# e202var-receiver-v1.net
KiCad netlist of a schematic drawn in EAGLE
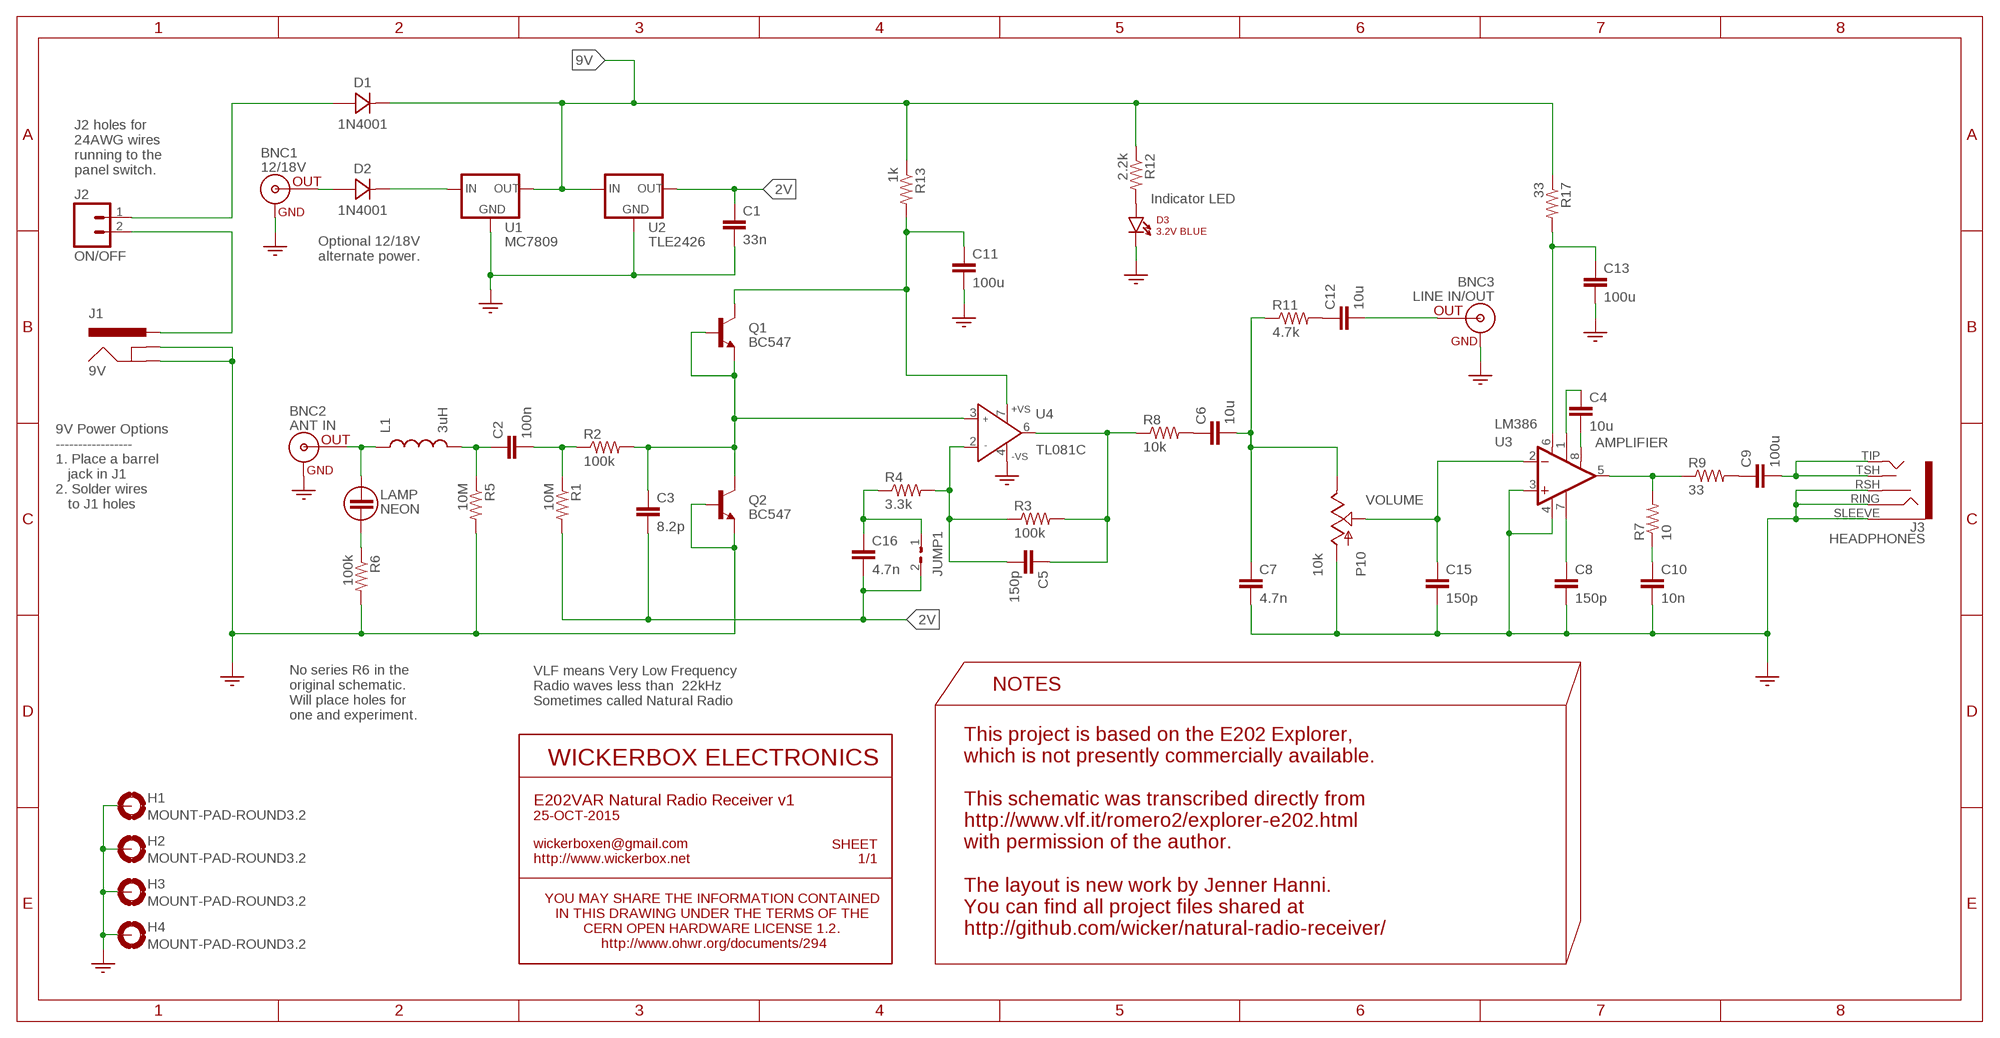
[diagram p0: schematic, sheet 1]

(export (version "E")
  (design (tool "Eeschema 10.0.6"))
  (components
    (comp (ref "BNC1")
      (value "12/18V")
      (footprint "eagle-import:BNC-MOLEX-SD-73100")
      (libsource (lib "eagle-import") (part "BNC-MOLEX-SD-73100"))
    )
    (comp (ref "BNC2")
      (value "ANT IN")
      (footprint "eagle-import:BNC-MOLEX-SD-73100")
      (libsource (lib "eagle-import") (part "BNC-MOLEX-SD-73100"))
    )
    (comp (ref "BNC3")
      (value "LINE IN/OUT")
      (footprint "eagle-import:BNC-MOLEX-SD-73100")
      (libsource (lib "eagle-import") (part "BNC-MOLEX-SD-73100"))
    )
    (comp (ref "C1")
      (value "33n")
      (footprint "eagle-import:CAP-RADIAL-5MM-NONPOL")
      (libsource (lib "eagle-import") (part "CAPACITOR5MM"))
    )
    (comp (ref "C2")
      (value "100n")
      (footprint "eagle-import:CAP-RADIAL-5MM-NONPOL")
      (libsource (lib "eagle-import") (part "CAPACITOR5MM"))
    )
    (comp (ref "C3")
      (value "8.2p")
      (footprint "eagle-import:CAP-RADIAL-5MM-NONPOL")
      (libsource (lib "eagle-import") (part "CAPACITOR5MM"))
    )
    (comp (ref "C4")
      (value "10u")
      (footprint "eagle-import:CAP-RADIAL-2.5MM-NONPOL")
      (libsource (lib "eagle-import") (part "CAPACITOR2.5MM"))
    )
    (comp (ref "C5")
      (value "150p")
      (footprint "eagle-import:CAP-RADIAL-2.5MM-NONPOL")
      (libsource (lib "eagle-import") (part "CAPACITOR2.5MM"))
    )
    (comp (ref "C6")
      (value "10u")
      (footprint "eagle-import:CAP-RADIAL-2.5MM-NONPOL")
      (libsource (lib "eagle-import") (part "CAPACITOR2.5MM"))
    )
    (comp (ref "C7")
      (value "4.7n")
      (footprint "eagle-import:CAP-RADIAL-5MM-NONPOL")
      (libsource (lib "eagle-import") (part "CAPACITOR5MM"))
    )
    (comp (ref "C8")
      (value "150p")
      (footprint "eagle-import:CAP-RADIAL-2.5MM-NONPOL")
      (libsource (lib "eagle-import") (part "CAPACITOR2.5MM"))
    )
    (comp (ref "C9")
      (value "100u")
      (footprint "eagle-import:CAP-RADIAL-5MM-NONPOL")
      (libsource (lib "eagle-import") (part "CAPACITOR5MM"))
    )
    (comp (ref "C10")
      (value "10n")
      (footprint "eagle-import:CAP-RADIAL-2.5MM-NONPOL")
      (libsource (lib "eagle-import") (part "CAPACITOR2.5MM"))
    )
    (comp (ref "C11")
      (value "100u")
      (footprint "eagle-import:CAP-RADIAL-5MM-NONPOL")
      (libsource (lib "eagle-import") (part "CAPACITOR5MM"))
    )
    (comp (ref "C12")
      (value "10u")
      (footprint "eagle-import:CAP-RADIAL-2.5MM-NONPOL")
      (libsource (lib "eagle-import") (part "CAPACITOR2.5MM"))
    )
    (comp (ref "C13")
      (value "100u")
      (footprint "eagle-import:CAP-RADIAL-5MM-NONPOL")
      (libsource (lib "eagle-import") (part "CAPACITOR5MM"))
    )
    (comp (ref "C15")
      (value "150p")
      (footprint "eagle-import:CAP-RADIAL-2.5MM-NONPOL")
      (libsource (lib "eagle-import") (part "CAPACITOR2.5MM"))
    )
    (comp (ref "C16")
      (value "4.7n")
      (footprint "eagle-import:CAP-RADIAL-5MM-NONPOL")
      (libsource (lib "eagle-import") (part "CAPACITOR5MM"))
    )
    (comp (ref "D1")
      (value "1N4001")
      (footprint "eagle-import:DIODE-DO41")
      (libsource (lib "eagle-import") (part "DIODE"))
    )
    (comp (ref "D2")
      (value "1N4001")
      (footprint "eagle-import:DIODE-DO41")
      (libsource (lib "eagle-import") (part "DIODE"))
    )
    (comp (ref "D3")
      (value "3.2V BLUE")
      (footprint "eagle-import:LED-2PIN-0.1IN")
      (libsource (lib "eagle-import") (part "LED"))
    )
    (comp (ref "H1")
      (value "MOUNT-PAD-ROUND3.2")
      (footprint "eagle-import:3,2-PAD")
      (libsource (lib "eagle-import") (part "MOUNT-PAD-ROUND3.2"))
    )
    (comp (ref "H2")
      (value "MOUNT-PAD-ROUND3.2")
      (footprint "eagle-import:3,2-PAD")
      (libsource (lib "eagle-import") (part "MOUNT-PAD-ROUND3.2"))
    )
    (comp (ref "H3")
      (value "MOUNT-PAD-ROUND3.2")
      (footprint "eagle-import:3,2-PAD")
      (libsource (lib "eagle-import") (part "MOUNT-PAD-ROUND3.2"))
    )
    (comp (ref "H4")
      (value "MOUNT-PAD-ROUND3.2")
      (footprint "eagle-import:3,2-PAD")
      (libsource (lib "eagle-import") (part "MOUNT-PAD-ROUND3.2"))
    )
    (comp (ref "J1")
      (value "9V")
      (footprint "eagle-import:JACK-POWER")
      (libsource (lib "eagle-import") (part "JACK-POWER-BARREL"))
    )
    (comp (ref "J2")
      (value "ON/OFF")
      (footprint "eagle-import:CONN-2PIN-0.1IN")
      (libsource (lib "eagle-import") (part "CONN-2PIN"))
    )
    (comp (ref "J3")
      (value "HEADPHONES")
      (footprint "eagle-import:JACK-AUDIO-5PIN")
      (libsource (lib "eagle-import") (part "JACK-AUDIO"))
    )
    (comp (ref "JUMP1")
      (value "HPF")
      (footprint "eagle-import:CONN-2PIN-0.1IN")
      (libsource (lib "eagle-import") (part "JUMPER-SHUNT"))
    )
    (comp (ref "L1")
      (value "3uH")
      (footprint "eagle-import:RES-CF14-TH")
      (libsource (lib "eagle-import") (part "INDUCTOR"))
    )
    (comp (ref "LAMP")
      (value "NEON")
      (footprint "eagle-import:LAMP-2PIN-0.1IN")
      (libsource (lib "eagle-import") (part "LAMP-NEON"))
    )
    (comp (ref "P10")
      (value "10k")
      (footprint "eagle-import:POT-3PIN-LINEAR")
      (libsource (lib "eagle-import") (part "POT-P160KN-0QC15B10K"))
    )
    (comp (ref "Q1")
      (value "BC547")
      (footprint "eagle-import:TO-92-AMMO")
      (libsource (lib "eagle-import") (part "BJT-NPN"))
    )
    (comp (ref "Q2")
      (value "BC547")
      (footprint "eagle-import:TO-92-AMMO")
      (libsource (lib "eagle-import") (part "BJT-NPN"))
    )
    (comp (ref "R1")
      (value "10M")
      (footprint "eagle-import:RES-CF14-TH")
      (libsource (lib "eagle-import") (part "RESISTOR"))
    )
    (comp (ref "R2")
      (value "100k")
      (footprint "eagle-import:RES-CF14-TH")
      (libsource (lib "eagle-import") (part "RESISTOR"))
    )
    (comp (ref "R3")
      (value "100k")
      (footprint "eagle-import:RES-CF14-TH")
      (libsource (lib "eagle-import") (part "RESISTOR"))
    )
    (comp (ref "R4")
      (value "3.3k")
      (footprint "eagle-import:RES-CF14-TH")
      (libsource (lib "eagle-import") (part "RESISTOR"))
    )
    (comp (ref "R5")
      (value "10M")
      (footprint "eagle-import:RES-CF14-TH")
      (libsource (lib "eagle-import") (part "RESISTOR"))
    )
    (comp (ref "R6")
      (value "100k")
      (footprint "eagle-import:RES-CF14-TH")
      (libsource (lib "eagle-import") (part "RESISTOR"))
    )
    (comp (ref "R7")
      (value "10")
      (footprint "eagle-import:RES-CF14-TH")
      (libsource (lib "eagle-import") (part "RESISTOR"))
    )
    (comp (ref "R8")
      (value "10k")
      (footprint "eagle-import:RES-CF14-TH")
      (libsource (lib "eagle-import") (part "RESISTOR"))
    )
    (comp (ref "R9")
      (value "33")
      (footprint "eagle-import:RES-CF14-TH")
      (libsource (lib "eagle-import") (part "RESISTOR"))
    )
    (comp (ref "R11")
      (value "4.7k")
      (footprint "eagle-import:RES-CF14-TH")
      (libsource (lib "eagle-import") (part "RESISTOR"))
    )
    (comp (ref "R12")
      (value "2.2k")
      (footprint "eagle-import:RES-CF14-TH")
      (libsource (lib "eagle-import") (part "RESISTOR"))
    )
    (comp (ref "R13")
      (value "1k")
      (footprint "eagle-import:RES-CF14-TH")
      (libsource (lib "eagle-import") (part "RESISTOR"))
    )
    (comp (ref "R17")
      (value "33")
      (footprint "eagle-import:RES-CF14-TH")
      (libsource (lib "eagle-import") (part "RESISTOR"))
    )
    (comp (ref "U1")
      (value "MC7809")
      (footprint "eagle-import:TO-220")
      (libsource (lib "eagle-import") (part "VOLTREG-MC7809"))
    )
    (comp (ref "U2")
      (value "TLE2426")
      (footprint "eagle-import:DIP-08")
      (libsource (lib "eagle-import") (part "VOLTREG-TLE2426"))
    )
    (comp (ref "U3")
      (value "LM386")
      (footprint "eagle-import:DIP-08")
      (libsource (lib "eagle-import") (part "AMP-AUDIO-LM386"))
    )
    (comp (ref "U4")
      (value "TL081C")
      (footprint "eagle-import:DIP-08")
      (libsource (lib "eagle-import") (part "AMP-JFET-TL081CP"))
    )
  )
  (nets
    (net (code "1") (name "2V") (class "Default")
      (node (ref "C1") (pin "1") (pinfunction "1_1") (pintype "passive"))
      (node (ref "C16") (pin "2") (pinfunction "2_2") (pintype "passive"))
      (node (ref "C3") (pin "2") (pinfunction "2_2") (pintype "passive"))
      (node (ref "JUMP1") (pin "2") (pinfunction "2_2") (pintype "passive"))
      (node (ref "R1") (pin "P$2") (pinfunction "2_P$2") (pintype "passive"))
      (node (ref "U2") (pin "1") (pinfunction "OUT_1") (pintype "output"))
    )
    (net (code "2") (name "9V") (class "Default")
      (node (ref "D1") (pin "C") (pinfunction "CATHODE_C") (pintype "passive"))
      (node (ref "R12") (pin "P$1") (pinfunction "1_P$1") (pintype "passive"))
      (node (ref "R13") (pin "P$1") (pinfunction "1_P$1") (pintype "passive"))
      (node (ref "R17") (pin "P$1") (pinfunction "1_P$1") (pintype "passive"))
      (node (ref "U1") (pin "OUT") (pinfunction "OUT_OUT") (pintype "output"))
      (node (ref "U2") (pin "3") (pinfunction "IN_3") (pintype "input"))
    )
    (net (code "3") (name "GND") (class "Default")
      (node (ref "BNC1") (pin "GND") (pinfunction "GND_GND") (pintype "bidirectional"))
      (node (ref "BNC1") (pin "GND1") (pinfunction "GND_GND1") (pintype "bidirectional"))
      (node (ref "BNC2") (pin "GND") (pinfunction "GND_GND") (pintype "bidirectional"))
      (node (ref "BNC2") (pin "GND1") (pinfunction "GND_GND1") (pintype "bidirectional"))
      (node (ref "BNC3") (pin "GND") (pinfunction "GND_GND") (pintype "bidirectional"))
      (node (ref "BNC3") (pin "GND1") (pinfunction "GND_GND1") (pintype "bidirectional"))
      (node (ref "C1") (pin "2") (pinfunction "2_2") (pintype "passive"))
      (node (ref "C10") (pin "2") (pinfunction "2_2") (pintype "passive"))
      (node (ref "C11") (pin "2") (pinfunction "2_2") (pintype "passive"))
      (node (ref "C13") (pin "2") (pinfunction "2_2") (pintype "passive"))
      (node (ref "C15") (pin "2") (pinfunction "2_2") (pintype "passive"))
      (node (ref "C7") (pin "2") (pinfunction "2_2") (pintype "passive"))
      (node (ref "C8") (pin "2") (pinfunction "2_2") (pintype "passive"))
      (node (ref "D3") (pin "C") (pinfunction "CATHODE_C") (pintype "bidirectional"))
      (node (ref "H1") (pin "B3,2") (pinfunction "MOUNT_B3,2") (pintype "passive"))
      (node (ref "H2") (pin "B3,2") (pinfunction "MOUNT_B3,2") (pintype "passive"))
      (node (ref "H3") (pin "B3,2") (pinfunction "MOUNT_B3,2") (pintype "passive"))
      (node (ref "H4") (pin "B3,2") (pinfunction "MOUNT_B3,2") (pintype "passive"))
      (node (ref "J1") (pin "GND") (pinfunction "GND_GND") (pintype "bidirectional"))
      (node (ref "J1") (pin "GNDBREAK") (pinfunction "GNDBREAK_GNDBREAK") (pintype "bidirectional"))
      (node (ref "J3") (pin "RING") (pinfunction "RING_RING") (pintype "bidirectional"))
      (node (ref "J3") (pin "RSH") (pinfunction "RSH_RSH") (pintype "bidirectional"))
      (node (ref "J3") (pin "SLEEVE") (pinfunction "SLEEVE_SLEEVE") (pintype "bidirectional"))
      (node (ref "P10") (pin "1") (pinfunction "A_1") (pintype "passive"))
      (node (ref "Q2") (pin "2") (pinfunction "B_2") (pintype "passive"))
      (node (ref "Q2") (pin "3") (pinfunction "E_3") (pintype "passive"))
      (node (ref "R5") (pin "P$2") (pinfunction "2_P$2") (pintype "passive"))
      (node (ref "R6") (pin "P$2") (pinfunction "2_P$2") (pintype "passive"))
      (node (ref "U1") (pin "GND") (pinfunction "GND_GND") (pintype "input"))
      (node (ref "U2") (pin "2") (pinfunction "GND_2") (pintype "input"))
      (node (ref "U3") (pin "3") (pinfunction "+IN_3") (pintype "input"))
      (node (ref "U3") (pin "4") (pinfunction "V-_4") (pintype "power_in"))
      (node (ref "U4") (pin "4") (pinfunction "-VS_4") (pintype "input"))
    )
    (net (code "4") (name "Net-(BNC1-OUT)") (class "Default")
      (node (ref "BNC1") (pin "SIGNAL") (pinfunction "OUT_SIGNAL") (pintype "bidirectional"))
      (node (ref "D2") (pin "A") (pinfunction "ANODE_A") (pintype "passive"))
    )
    (net (code "5") (name "Net-(BNC2-OUT)") (class "Default")
      (node (ref "BNC2") (pin "SIGNAL") (pinfunction "OUT_SIGNAL") (pintype "bidirectional"))
      (node (ref "L1") (pin "P$1") (pinfunction "1_P$1") (pintype "passive"))
      (node (ref "LAMP") (pin "A") (pinfunction "1_A") (pintype "passive"))
    )
    (net (code "6") (name "Net-(BNC3-OUT)") (class "Default")
      (node (ref "BNC3") (pin "SIGNAL") (pinfunction "OUT_SIGNAL") (pintype "bidirectional"))
      (node (ref "C12") (pin "2") (pinfunction "2_2") (pintype "passive"))
    )
    (net (code "7") (name "Net-(C4-Pad1)") (class "Default")
      (node (ref "C4") (pin "1") (pinfunction "1_1") (pintype "passive"))
      (node (ref "U3") (pin "1") (pinfunction "GAIN_1") (pintype "bidirectional"))
    )
    (net (code "8") (name "Net-(C4-Pad2)") (class "Default")
      (node (ref "C4") (pin "2") (pinfunction "2_2") (pintype "passive"))
      (node (ref "U3") (pin "8") (pinfunction "GAIN_8") (pintype "bidirectional"))
    )
    (net (code "9") (name "Net-(C9-Pad2)") (class "Default")
      (node (ref "C9") (pin "2") (pinfunction "2_2") (pintype "passive"))
      (node (ref "J3") (pin "TIP") (pinfunction "TIP_TIP") (pintype "bidirectional"))
      (node (ref "J3") (pin "TSH") (pinfunction "TSH_TSH") (pintype "bidirectional"))
    )
    (net (code "10") (name "Net-(D1-ANODE)") (class "Default")
      (node (ref "D1") (pin "A") (pinfunction "ANODE_A") (pintype "passive"))
      (node (ref "J2") (pin "1") (pinfunction "1_1") (pintype "passive"))
    )
    (net (code "11") (name "Net-(D2-CATHODE)") (class "Default")
      (node (ref "D2") (pin "C") (pinfunction "CATHODE_C") (pintype "passive"))
      (node (ref "U1") (pin "IN") (pinfunction "IN_IN") (pintype "input"))
    )
    (net (code "12") (name "Net-(D3-ANODE)") (class "Default")
      (node (ref "D3") (pin "A") (pinfunction "ANODE_A") (pintype "bidirectional"))
      (node (ref "R12") (pin "P$2") (pinfunction "2_P$2") (pintype "passive"))
    )
    (net (code "13") (name "Net-(J1-PadPWR)") (class "Default")
      (node (ref "J1") (pin "PWR") (pinfunction "PWR_PWR") (pintype "bidirectional"))
      (node (ref "J2") (pin "2") (pinfunction "2_2") (pintype "passive"))
    )
    (net (code "14") (name "Net-(L1-2)") (class "Default")
      (node (ref "C2") (pin "1") (pinfunction "1_1") (pintype "passive"))
      (node (ref "L1") (pin "P$2") (pinfunction "2_P$2") (pintype "passive"))
      (node (ref "R5") (pin "P$1") (pinfunction "1_P$1") (pintype "passive"))
    )
    (net (code "15") (name "Net-(LAMP-2)") (class "Default")
      (node (ref "LAMP") (pin "C") (pinfunction "2_C") (pintype "passive"))
      (node (ref "R6") (pin "P$1") (pinfunction "1_P$1") (pintype "passive"))
    )
    (net (code "16") (name "Net-(P10-E)") (class "Default")
      (node (ref "C6") (pin "2") (pinfunction "2_2") (pintype "passive"))
      (node (ref "C7") (pin "1") (pinfunction "1_1") (pintype "passive"))
      (node (ref "P10") (pin "3") (pinfunction "E_3") (pintype "passive"))
      (node (ref "R11") (pin "P$1") (pinfunction "1_P$1") (pintype "passive"))
    )
    (net (code "17") (name "Net-(P10-S)") (class "Default")
      (node (ref "C15") (pin "1") (pinfunction "1_1") (pintype "passive"))
      (node (ref "P10") (pin "2") (pinfunction "S_2") (pintype "passive"))
      (node (ref "U3") (pin "2") (pinfunction "-IN_2") (pintype "input"))
    )
    (net (code "18") (name "Net-(Q1-B)") (class "Default")
      (node (ref "C3") (pin "1") (pinfunction "1_1") (pintype "passive"))
      (node (ref "Q1") (pin "2") (pinfunction "B_2") (pintype "passive"))
      (node (ref "Q1") (pin "3") (pinfunction "E_3") (pintype "passive"))
      (node (ref "Q2") (pin "1") (pinfunction "C_1") (pintype "passive"))
      (node (ref "R2") (pin "P$2") (pinfunction "2_P$2") (pintype "passive"))
      (node (ref "U4") (pin "3") (pinfunction "IN+_3") (pintype "input"))
    )
    (net (code "19") (name "Net-(Q1-C)") (class "Default")
      (node (ref "C11") (pin "1") (pinfunction "1_1") (pintype "passive"))
      (node (ref "Q1") (pin "1") (pinfunction "C_1") (pintype "passive"))
      (node (ref "R13") (pin "P$2") (pinfunction "2_P$2") (pintype "passive"))
      (node (ref "U4") (pin "7") (pinfunction "+VS_7") (pintype "input"))
    )
    (net (code "20") (name "Net-(R1-1)") (class "Default")
      (node (ref "C2") (pin "2") (pinfunction "2_2") (pintype "passive"))
      (node (ref "R1") (pin "P$1") (pinfunction "1_P$1") (pintype "passive"))
      (node (ref "R2") (pin "P$1") (pinfunction "1_P$1") (pintype "passive"))
    )
    (net (code "21") (name "Net-(R3-1)") (class "Default")
      (node (ref "C5") (pin "2") (pinfunction "2_2") (pintype "passive"))
      (node (ref "R3") (pin "P$1") (pinfunction "1_P$1") (pintype "passive"))
      (node (ref "R4") (pin "P$2") (pinfunction "2_P$2") (pintype "passive"))
      (node (ref "U4") (pin "2") (pinfunction "IN-_2") (pintype "input"))
    )
    (net (code "22") (name "Net-(R3-2)") (class "Default")
      (node (ref "C5") (pin "1") (pinfunction "1_1") (pintype "passive"))
      (node (ref "R3") (pin "P$2") (pinfunction "2_P$2") (pintype "passive"))
      (node (ref "R8") (pin "P$1") (pinfunction "1_P$1") (pintype "passive"))
      (node (ref "U4") (pin "6") (pinfunction "OUT_6") (pintype "output"))
    )
    (net (code "23") (name "Net-(R4-1)") (class "Default")
      (node (ref "C16") (pin "1") (pinfunction "1_1") (pintype "passive"))
      (node (ref "JUMP1") (pin "1") (pinfunction "1_1") (pintype "passive"))
      (node (ref "R4") (pin "P$1") (pinfunction "1_P$1") (pintype "passive"))
    )
    (net (code "24") (name "Net-(R7-1)") (class "Default")
      (node (ref "C10") (pin "1") (pinfunction "1_1") (pintype "passive"))
      (node (ref "R7") (pin "P$1") (pinfunction "1_P$1") (pintype "passive"))
    )
    (net (code "25") (name "Net-(R7-2)") (class "Default")
      (node (ref "R7") (pin "P$2") (pinfunction "2_P$2") (pintype "passive"))
      (node (ref "R9") (pin "P$1") (pinfunction "1_P$1") (pintype "passive"))
      (node (ref "U3") (pin "5") (pinfunction "OUT_5") (pintype "output"))
    )
    (net (code "26") (name "Net-(R8-2)") (class "Default")
      (node (ref "C6") (pin "1") (pinfunction "1_1") (pintype "passive"))
      (node (ref "R8") (pin "P$2") (pinfunction "2_P$2") (pintype "passive"))
    )
    (net (code "27") (name "Net-(R9-2)") (class "Default")
      (node (ref "C9") (pin "1") (pinfunction "1_1") (pintype "passive"))
      (node (ref "R9") (pin "P$2") (pinfunction "2_P$2") (pintype "passive"))
    )
    (net (code "28") (name "Net-(R11-2)") (class "Default")
      (node (ref "C12") (pin "1") (pinfunction "1_1") (pintype "passive"))
      (node (ref "R11") (pin "P$2") (pinfunction "2_P$2") (pintype "passive"))
    )
    (net (code "29") (name "Net-(R17-2)") (class "Default")
      (node (ref "C13") (pin "1") (pinfunction "1_1") (pintype "passive"))
      (node (ref "R17") (pin "P$2") (pinfunction "2_P$2") (pintype "passive"))
      (node (ref "U3") (pin "6") (pinfunction "V+_6") (pintype "power_in"))
    )
    (net (code "30") (name "Net-(U3-BP)") (class "Default")
      (node (ref "C8") (pin "1") (pinfunction "1_1") (pintype "passive"))
      (node (ref "U3") (pin "7") (pinfunction "BP_7") (pintype "bidirectional"))
    )
  )
)
